# uart_optoizolation.net
KiCad netlist of a schematic drawn in Altium Designer
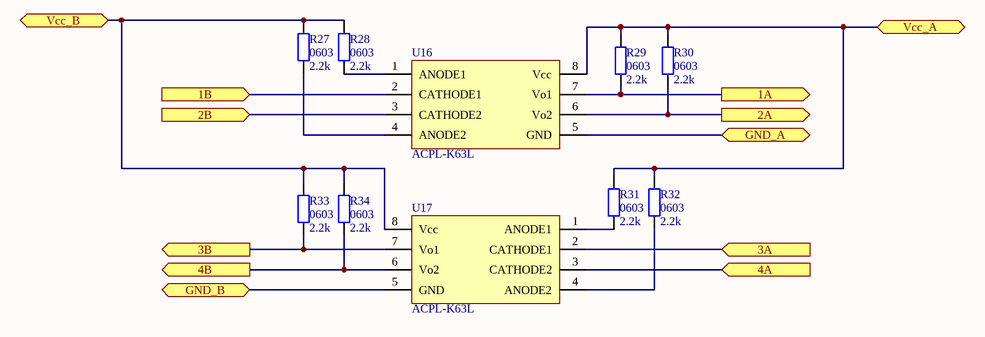
[diagram p0: uart_optoizolation.SchDoc]

(export (version "E")
  (design (tool "Eeschema 10.0.6"))
  (components
    (comp (ref "R27")
      (value "0603")
      (footprint "SMD_Resistor_0603")
      (description "Resistor")
      (fields (field (name "ALTIUM_VALUE") "2.2k") (field (name "PUBLISHER") "Altium Limited"))
      (libsource (lib "Miscellaneous Devices") (part "Res2"))
    )
    (comp (ref "R28")
      (value "0603")
      (footprint "SMD_Resistor_0603")
      (description "Resistor")
      (fields (field (name "ALTIUM_VALUE") "2.2k") (field (name "PUBLISHER") "Altium Limited"))
      (libsource (lib "Miscellaneous Devices") (part "Res2"))
    )
    (comp (ref "R29")
      (value "0603")
      (footprint "SMD_Resistor_0603")
      (description "Resistor")
      (fields (field (name "ALTIUM_VALUE") "2.2k") (field (name "PUBLISHER") "Altium Limited"))
      (libsource (lib "Miscellaneous Devices") (part "Res2"))
    )
    (comp (ref "R30")
      (value "0603")
      (footprint "SMD_Resistor_0603")
      (description "Resistor")
      (fields (field (name "ALTIUM_VALUE") "2.2k") (field (name "PUBLISHER") "Altium Limited"))
      (libsource (lib "Miscellaneous Devices") (part "Res2"))
    )
    (comp (ref "R31")
      (value "0603")
      (footprint "SMD_Resistor_0603")
      (description "Resistor")
      (fields (field (name "ALTIUM_VALUE") "2.2k") (field (name "PUBLISHER") "Altium Limited"))
      (libsource (lib "Miscellaneous Devices") (part "Res2"))
    )
    (comp (ref "R32")
      (value "0603")
      (footprint "SMD_Resistor_0603")
      (description "Resistor")
      (fields (field (name "ALTIUM_VALUE") "2.2k") (field (name "PUBLISHER") "Altium Limited"))
      (libsource (lib "Miscellaneous Devices") (part "Res2"))
    )
    (comp (ref "R33")
      (value "0603")
      (footprint "SMD_Resistor_0603")
      (description "Resistor")
      (fields (field (name "ALTIUM_VALUE") "2.2k") (field (name "PUBLISHER") "Altium Limited"))
      (libsource (lib "Miscellaneous Devices") (part "Res2"))
    )
    (comp (ref "R34")
      (value "0603")
      (footprint "SMD_Resistor_0603")
      (description "Resistor")
      (fields (field (name "ALTIUM_VALUE") "2.2k") (field (name "PUBLISHER") "Altium Limited"))
      (libsource (lib "Miscellaneous Devices") (part "Res2"))
    )
    (comp (ref "U16")
      (value "ACPL-K63L")
      (footprint "SOIC-8_M")
      (description "High Speed LVTTL Compatible 3.3 Volt/5 Volt Optocouplers")
      (libsource (lib "") (part "ACPL-K63L_1"))
    )
    (comp (ref "U17")
      (value "ACPL-K63L")
      (footprint "SOIC-8_M")
      (description "High Speed LVTTL Compatible 3.3 Volt/5 Volt Optocouplers")
      (libsource (lib "GG") (part "ACPL-K63L"))
    )
  )
  (nets
    (net (code "1") (name "/1A") (class "Default")
      (node (ref "R29") (pin "1") (pinfunction "1_1") (pintype "passive"))
      (node (ref "U16") (pin "7") (pinfunction "Vo1_7") (pintype "power_in"))
    )
    (net (code "2") (name "/1B") (class "Default")
      (node (ref "U16") (pin "2") (pinfunction "CATHODE1_2") (pintype "power_in"))
    )
    (net (code "3") (name "/2A") (class "Default")
      (node (ref "R30") (pin "1") (pinfunction "1_1") (pintype "passive"))
      (node (ref "U16") (pin "6") (pinfunction "Vo2_6") (pintype "power_in"))
    )
    (net (code "4") (name "/2B") (class "Default")
      (node (ref "U16") (pin "3") (pinfunction "CATHODE2_3") (pintype "power_in"))
    )
    (net (code "5") (name "/3A") (class "Default")
      (node (ref "U17") (pin "2") (pinfunction "CATHODE1_2") (pintype "power_in"))
    )
    (net (code "6") (name "/3B") (class "Default")
      (node (ref "R33") (pin "1") (pinfunction "1_1") (pintype "passive"))
      (node (ref "U17") (pin "7") (pinfunction "Vo1_7") (pintype "power_in"))
    )
    (net (code "7") (name "/4A") (class "Default")
      (node (ref "U17") (pin "3") (pinfunction "CATHODE2_3") (pintype "power_in"))
    )
    (net (code "8") (name "/4B") (class "Default")
      (node (ref "R34") (pin "1") (pinfunction "1_1") (pintype "passive"))
      (node (ref "U17") (pin "6") (pinfunction "Vo2_6") (pintype "power_in"))
    )
    (net (code "9") (name "/GND_A") (class "Default")
      (node (ref "U16") (pin "5") (pinfunction "GND_5") (pintype "power_in"))
    )
    (net (code "10") (name "/GND_B") (class "Default")
      (node (ref "U17") (pin "5") (pinfunction "GND_5") (pintype "power_in"))
    )
    (net (code "11") (name "/Vcc_A") (class "Default")
      (node (ref "R29") (pin "2") (pinfunction "2_2") (pintype "passive"))
      (node (ref "R30") (pin "2") (pinfunction "2_2") (pintype "passive"))
      (node (ref "R31") (pin "2") (pinfunction "2_2") (pintype "passive"))
      (node (ref "R32") (pin "2") (pinfunction "2_2") (pintype "passive"))
      (node (ref "U16") (pin "8") (pinfunction "Vcc_8") (pintype "power_in"))
    )
    (net (code "12") (name "/Vcc_B") (class "Default")
      (node (ref "R27") (pin "2") (pinfunction "2_2") (pintype "passive"))
      (node (ref "R28") (pin "2") (pinfunction "2_2") (pintype "passive"))
      (node (ref "R33") (pin "2") (pinfunction "2_2") (pintype "passive"))
      (node (ref "R34") (pin "2") (pinfunction "2_2") (pintype "passive"))
      (node (ref "U17") (pin "8") (pinfunction "Vcc_8") (pintype "power_in"))
    )
    (net (code "13") (name "Net-(U16-ANODE1)") (class "Default")
      (node (ref "R28") (pin "1") (pinfunction "1_1") (pintype "passive"))
      (node (ref "U16") (pin "1") (pinfunction "ANODE1_1") (pintype "power_in"))
    )
    (net (code "14") (name "Net-(U16-ANODE2)") (class "Default")
      (node (ref "R27") (pin "1") (pinfunction "1_1") (pintype "passive"))
      (node (ref "U16") (pin "4") (pinfunction "ANODE2_4") (pintype "power_in"))
    )
    (net (code "15") (name "Net-(U17-ANODE1)") (class "Default")
      (node (ref "R31") (pin "1") (pinfunction "1_1") (pintype "passive"))
      (node (ref "U17") (pin "1") (pinfunction "ANODE1_1") (pintype "power_in"))
    )
    (net (code "16") (name "Net-(U17-ANODE2)") (class "Default")
      (node (ref "R32") (pin "1") (pinfunction "1_1") (pintype "passive"))
      (node (ref "U17") (pin "4") (pinfunction "ANODE2_4") (pintype "power_in"))
    )
  )
)
